# BQ24259RGER.net
KiCad netlist of a schematic drawn in Altium Designer
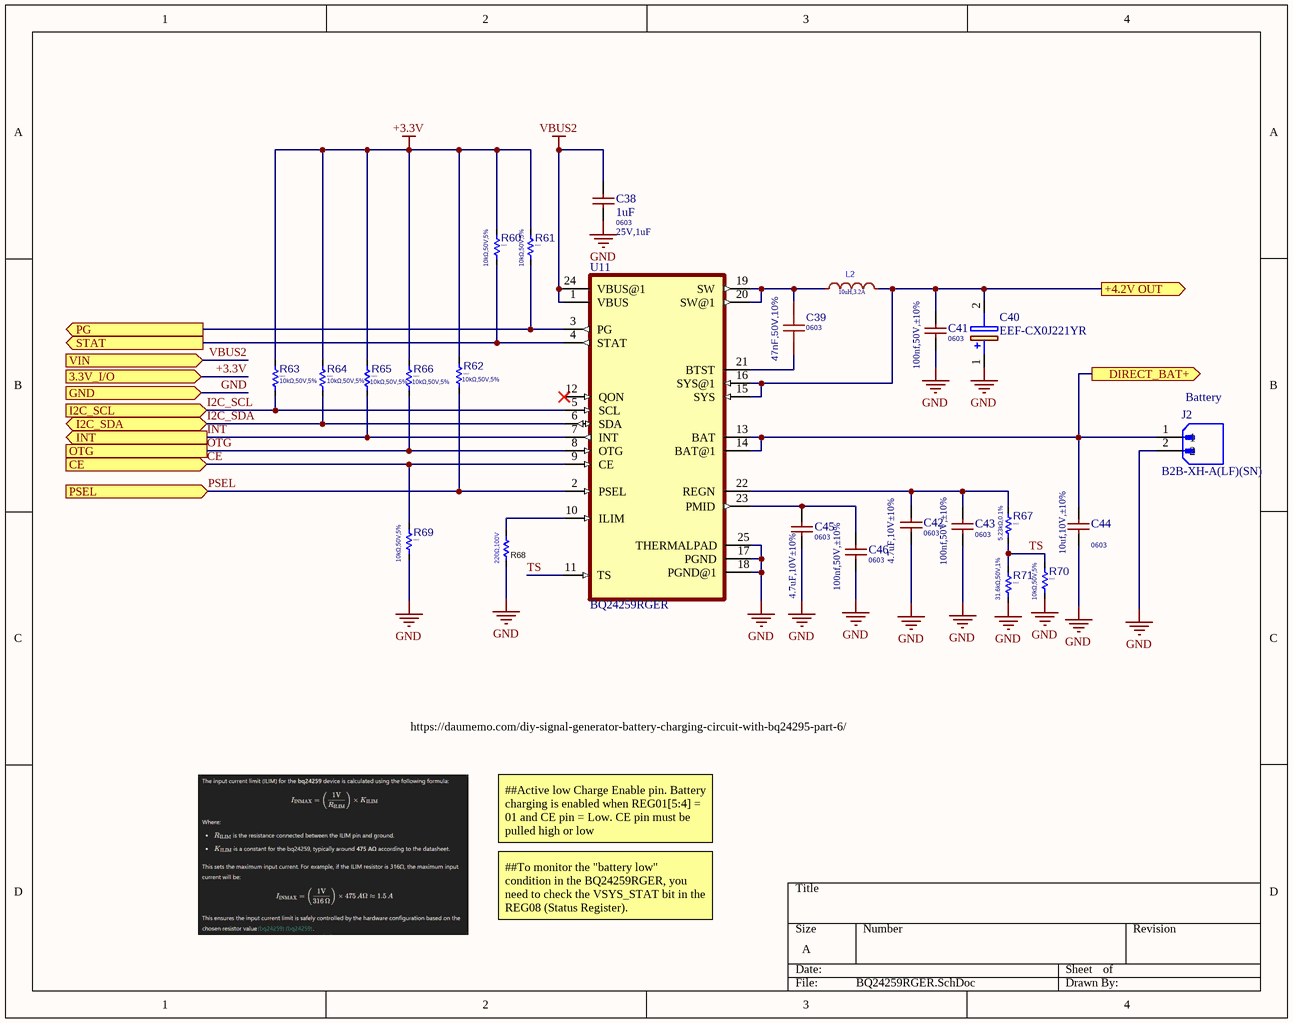
[diagram p0: BQ24259RGER.SchDoc]

(export (version "E")
  (design (tool "Eeschema 10.0.6"))
  (components
    (comp (ref "C38")
      (value "1uF")
      (footprint "CAPC1608X90N")
      (description "25V 1uF X7R ±10% 0603 Multilayer Ceramic Capacitors MLCC - SMD/SMT ROHS")
      (fields
        (field (name "MANUFACTURER") "FH (Guangdong Fenghua Advanced Tech)")
        (field (name "MPN") "0603B105K250NT")
        (field (name "PACKAGE") "0603")
        (field (name "ALTIUM_VALUE") "25V,1uF")
      )
      (libsource (lib "RCL") (part "0603B105K250NT"))
    )
    (comp (ref "C39")
      (value "47nF,50V,10%")
      (footprint "C0603")
      (description "50V 47nF X7R ±10% 0603 Multilayer Ceramic Capacitors MLCC - SMD/SMT ROHS")
      (fields
        (field (name "MANUFACTURER") "SAMSUNG")
        (field (name "MPN") "CL10B473KB8NNNC")
        (field (name "PACKAGE") "0603")
      )
      (libsource (lib "RCL") (part "CL10B473KB8NNNC"))
    )
    (comp (ref "C40")
      (value "EEF-CX0J221YR")
      (footprint "CAPPM7343X200N")
      (description "Capacitor Polarised")
      (libsource (lib "RCL") (part "EEF-CX0J221YR"))
    )
    (comp (ref "C41")
      (value "100nf,50V,±10%")
      (footprint "C0603")
      (description "50V 100nF X7R ±10% 0603 Multilayer Ceramic Capacitors MLCC - SMD/SMT ROHS")
      (fields
        (field (name "MPN") "603-CC603KRX7R9BB104")
        (field (name "MANUFACTURER") "KEMET")
        (field (name "PACKAGE") "0603")
      )
      (libsource (lib "RCL") (part "CC0603KRX7R9BB104"))
    )
    (comp (ref "C42")
      (value "4.7uF,10V±10%")
      (footprint "C0603")
      (description "10V 4.7uF X7R ±10% 0603 Multilayer Ceramic Capacitors MLCC - SMD/SMT ROHS")
      (fields
        (field (name "MPN") "CL10A475KQ8NNNC")
        (field (name "MANUFACTURER") "Samsung Electro-Mechanics")
        (field (name "PACKAGE") "0603")
      )
      (libsource (lib "RCL") (part "0603B475K100NT"))
    )
    (comp (ref "C43")
      (value "100nf,50V,±10%")
      (footprint "C0603")
      (description "50V 100nF X7R ±10% 0603 Multilayer Ceramic Capacitors MLCC - SMD/SMT ROHS")
      (fields
        (field (name "MPN") "603-CC603KRX7R9BB104")
        (field (name "MANUFACTURER") "KEMET")
        (field (name "PACKAGE") "0603")
      )
      (libsource (lib "RCL") (part "CC0603KRX7R9BB104"))
    )
    (comp (ref "C44")
      (value "10uf,10V,±10%")
      (footprint "C0603")
      (description "10V 10uF X7R ±10% 0603 Multilayer Ceramic Capacitors MLCC - SMD/SMT ROHS")
      (fields
        (field (name "MPN") "603-CC603KRX7R9BB104")
        (field (name "MANUFACTURER") "KEMET")
        (field (name "PACKAGE") "0603")
      )
      (libsource (lib "RCL") (part "GRM188Z71A106KA73D"))
    )
    (comp (ref "C45")
      (value "4.7uF,10V±10%")
      (footprint "C0603")
      (description "10V 4.7uF X7R ±10% 0603 Multilayer Ceramic Capacitors MLCC - SMD/SMT ROHS")
      (fields
        (field (name "MPN") "CL10A475KQ8NNNC")
        (field (name "MANUFACTURER") "Samsung Electro-Mechanics")
        (field (name "PACKAGE") "0603")
      )
      (libsource (lib "RCL") (part "0603B475K100NT"))
    )
    (comp (ref "C46")
      (value "100nf,50V,±10%")
      (footprint "C0603")
      (description "50V 100nF X7R ±10% 0603 Multilayer Ceramic Capacitors MLCC - SMD/SMT ROHS")
      (fields
        (field (name "MPN") "603-CC603KRX7R9BB104")
        (field (name "MANUFACTURER") "KEMET")
        (field (name "PACKAGE") "0603")
      )
      (libsource (lib "RCL") (part "CC0603KRX7R9BB104"))
    )
    (comp (ref "J2")
      (value "B2B-XH-A(LF)(SN)")
      (footprint "JST_B2B-XH-A(LF)(SN)")
      (description "Connector Header Through Hole 2 position 0.098 (2.50mm)")
      (fields (field (name "MANUFACTURER") "JST Sales America Inc."))
      (libsource (lib "connector_button") (part "B2B-XH-A(LF)(SN)"))
    )
    (comp (ref "L2")
      (value "10uH,3.2A")
      (footprint "inductor_SMD,5.2x5.4mm")
      (description "3.2A 10uH Integrated molded inductor ±20% 3.5A SMD,5.2x5.4mm Power Inductors ROHS")
      (fields (field (name "MANUFACTURER") "cjiang") (field (name "MPN") "FXL0530-100-M"))
      (libsource (lib "RCL") (part "FXL0530-100-M"))
    )
    (comp (ref "R60")
      (value "10kΩ,50V,5%")
      (footprint "R0402")
      (description "62.5mW Thick Film Resistors 50V ±100ppm/℃ ±5% 10kΩ 0402 Chip Resistor - Surface Mount ROHS")
      (fields
        (field (name "MANUFACTURER") "YAGEO")
        (field (name "MPN") "RC0402JR-0710KL")
        (field (name "PACKAGE") "0402")
      )
      (libsource (lib "RCL") (part "RC0402JR-0710KL"))
    )
    (comp (ref "R61")
      (value "10kΩ,50V,5%")
      (footprint "R0402")
      (description "62.5mW Thick Film Resistors 50V ±100ppm/℃ ±5% 10kΩ 0402 Chip Resistor - Surface Mount ROHS")
      (fields
        (field (name "MANUFACTURER") "YAGEO")
        (field (name "MPN") "RC0402JR-0710KL")
        (field (name "PACKAGE") "0402")
      )
      (libsource (lib "RCL") (part "RC0402JR-0710KL"))
    )
    (comp (ref "R62")
      (value "10kΩ,50V,5%")
      (footprint "R0402")
      (description "62.5mW Thick Film Resistors 50V ±100ppm/℃ ±5% 10kΩ 0402 Chip Resistor - Surface Mount ROHS")
      (fields
        (field (name "MANUFACTURER") "YAGEO")
        (field (name "MPN") "RC0402JR-0710KL")
        (field (name "PACKAGE") "0402")
      )
      (libsource (lib "RCL") (part "RC0402JR-0710KL"))
    )
    (comp (ref "R63")
      (value "10kΩ,50V,5%")
      (footprint "R0402")
      (description "62.5mW Thick Film Resistors 50V ±100ppm/℃ ±5% 10kΩ 0402 Chip Resistor - Surface Mount ROHS")
      (fields
        (field (name "MANUFACTURER") "YAGEO")
        (field (name "MPN") "RC0402JR-0710KL")
        (field (name "PACKAGE") "0402")
      )
      (libsource (lib "RCL") (part "RC0402JR-0710KL"))
    )
    (comp (ref "R64")
      (value "10kΩ,50V,5%")
      (footprint "R0402")
      (description "62.5mW Thick Film Resistors 50V ±100ppm/℃ ±5% 10kΩ 0402 Chip Resistor - Surface Mount ROHS")
      (fields
        (field (name "MANUFACTURER") "YAGEO")
        (field (name "MPN") "RC0402JR-0710KL")
        (field (name "PACKAGE") "0402")
      )
      (libsource (lib "RCL") (part "RC0402JR-0710KL"))
    )
    (comp (ref "R65")
      (value "10kΩ,50V,5%")
      (footprint "R0402")
      (description "62.5mW Thick Film Resistors 50V ±100ppm/℃ ±5% 10kΩ 0402 Chip Resistor - Surface Mount ROHS")
      (fields
        (field (name "MANUFACTURER") "YAGEO")
        (field (name "MPN") "RC0402JR-0710KL")
        (field (name "PACKAGE") "0402")
      )
      (libsource (lib "RCL") (part "RC0402JR-0710KL"))
    )
    (comp (ref "R66")
      (value "10kΩ,50V,5%")
      (footprint "R0402")
      (description "62.5mW Thick Film Resistors 50V ±100ppm/℃ ±5% 10kΩ 0402 Chip Resistor - Surface Mount ROHS")
      (fields
        (field (name "MANUFACTURER") "YAGEO")
        (field (name "MPN") "RC0402JR-0710KL")
        (field (name "PACKAGE") "0402")
      )
      (libsource (lib "RCL") (part "RC0402JR-0710KL"))
    )
    (comp (ref "R67")
      (value "5.23kΩ,0.1%")
      (footprint "R0402")
      (description "63mW Thin Film Resistor ±25ppm/℃ ±0.1% 5.23kΩ 0402 Chip Resistor - Surface Mount ROHS")
      (fields
        (field (name "MANUFACTURER") "YAGEO")
        (field (name "MPN") "RT0402BRD075K23L")
        (field (name "PACKAGE") "0402")
      )
      (libsource (lib "RCL") (part "RT0402BRD075K23L"))
    )
    (comp (ref "R68")
      (value "220Ω,100V")
      (footprint "R0402")
      (description "100mW Thick Film Resistors 100V ±100ppm/℃ ±1% 220Ω 0402 Chip Resistor - Surface Mount ROHS")
      (fields (field (name "MANUFACTURER") "PANASONIC") (field (name "MPN") "ERJ2RKF2200X"))
      (libsource (lib "RCL") (part "ERJ2RKF2200X"))
    )
    (comp (ref "R69")
      (value "10kΩ,50V,5%")
      (footprint "R0402")
      (description "62.5mW Thick Film Resistors 50V ±100ppm/℃ ±5% 10kΩ 0402 Chip Resistor - Surface Mount ROHS")
      (fields
        (field (name "MANUFACTURER") "YAGEO")
        (field (name "MPN") "RC0402JR-0710KL")
        (field (name "PACKAGE") "0402")
      )
      (libsource (lib "RCL") (part "RC0402JR-0710KL"))
    )
    (comp (ref "R70")
      (value "10kΩ,50V,5%")
      (footprint "R0402")
      (description "62.5mW Thick Film Resistors 50V ±100ppm/℃ ±5% 10kΩ 0402 Chip Resistor - Surface Mount ROHS")
      (fields
        (field (name "MANUFACTURER") "YAGEO")
        (field (name "MPN") "RC0402JR-0710KL")
        (field (name "PACKAGE") "0402")
      )
      (libsource (lib "RCL") (part "RC0402JR-0710KL"))
    )
    (comp (ref "R71")
      (value "31.6kΩ,50V,1%")
      (footprint "R0402")
      (description "62.5mW Thick Film Resistors 50V ±100ppm/℃ ±1% 31.6kΩ 0402 Chip Resistor - Surface Mount ROHS")
      (fields
        (field (name "MANUFACTURER") "YAGEO")
        (field (name "MPN") "RC0402FR-0731K6L")
        (field (name "PACKAGE") "0402")
      )
      (libsource (lib "RCL") (part "RC0402FR-0731K6L"))
    )
    (comp (ref "U11")
      (value "BQ24259RGER")
      (footprint "QFN50P400X400X100-25N")
      (description "I2C controlled 2A single cell USB NVDC-1 charger with adjustable voltageUSB OTG")
      (fields (field (name "DIGI-KEY_PART_NUMBER") "296-43322-2-ND") (field (name "MF") "Texas Instruments"))
      (libsource (lib "IC") (part "BQ24259RGER"))
    )
  )
  (nets
    (net (code "1") (name "+3.3V") (class "Default")
      (node (ref "R60") (pin "2") (pinfunction "2_2") (pintype "passive"))
      (node (ref "R61") (pin "2") (pinfunction "2_2") (pintype "passive"))
      (node (ref "R62") (pin "2") (pinfunction "2_2") (pintype "passive"))
      (node (ref "R63") (pin "2") (pinfunction "2_2") (pintype "passive"))
      (node (ref "R64") (pin "2") (pinfunction "2_2") (pintype "passive"))
      (node (ref "R65") (pin "2") (pinfunction "2_2") (pintype "passive"))
      (node (ref "R66") (pin "2") (pinfunction "2_2") (pintype "passive"))
    )
    (net (code "2") (name "/+4.2V OUT") (class "Default")
      (node (ref "C40") (pin "2") (pinfunction "-_2") (pintype "passive"))
      (node (ref "C41") (pin "2") (pinfunction "2_2") (pintype "passive"))
      (node (ref "L2") (pin "2") (pinfunction "2_2") (pintype "passive"))
      (node (ref "U11") (pin "15") (pinfunction "SYS_15") (pintype "input"))
      (node (ref "U11") (pin "16") (pinfunction "SYS@1_16") (pintype "input"))
    )
    (net (code "3") (name "/CE") (class "Default")
      (node (ref "R69") (pin "2") (pinfunction "2_2") (pintype "passive"))
      (node (ref "U11") (pin "9") (pinfunction "CE_9") (pintype "input"))
    )
    (net (code "4") (name "/DIRECT_BAT+") (class "Default")
      (node (ref "C44") (pin "2") (pinfunction "2_2") (pintype "passive"))
      (node (ref "J2") (pin "1") (pinfunction "1_1") (pintype "passive"))
      (node (ref "U11") (pin "13") (pinfunction "BAT_13") (pintype "power_in"))
      (node (ref "U11") (pin "14") (pinfunction "BAT@1_14") (pintype "power_in"))
    )
    (net (code "5") (name "/I2C_SCL") (class "Default")
      (node (ref "R63") (pin "1") (pinfunction "1_1") (pintype "passive"))
      (node (ref "U11") (pin "5") (pinfunction "SCL_5") (pintype "input"))
    )
    (net (code "6") (name "/I2C_SDA") (class "Default")
      (node (ref "R64") (pin "1") (pinfunction "1_1") (pintype "passive"))
      (node (ref "U11") (pin "6") (pinfunction "SDA_6") (pintype "bidirectional"))
    )
    (net (code "7") (name "/INT") (class "Default")
      (node (ref "R65") (pin "1") (pinfunction "1_1") (pintype "passive"))
      (node (ref "U11") (pin "7") (pinfunction "INT_7") (pintype "output"))
    )
    (net (code "8") (name "/OTG") (class "Default")
      (node (ref "R66") (pin "1") (pinfunction "1_1") (pintype "passive"))
      (node (ref "U11") (pin "8") (pinfunction "OTG_8") (pintype "input"))
    )
    (net (code "9") (name "/PG") (class "Default")
      (node (ref "R61") (pin "1") (pinfunction "1_1") (pintype "passive"))
      (node (ref "U11") (pin "3") (pinfunction "PG_3") (pintype "output"))
    )
    (net (code "10") (name "/PSEL") (class "Default")
      (node (ref "R62") (pin "1") (pinfunction "1_1") (pintype "passive"))
      (node (ref "U11") (pin "2") (pinfunction "PSEL_2") (pintype "input"))
    )
    (net (code "11") (name "/STAT") (class "Default")
      (node (ref "R60") (pin "1") (pinfunction "1_1") (pintype "passive"))
      (node (ref "U11") (pin "4") (pinfunction "STAT_4") (pintype "output"))
    )
    (net (code "12") (name "/TS") (class "Default")
      (node (ref "R67") (pin "1") (pinfunction "1_1") (pintype "passive"))
      (node (ref "R70") (pin "2") (pinfunction "2_2") (pintype "passive"))
      (node (ref "R71") (pin "2") (pinfunction "2_2") (pintype "passive"))
      (node (ref "U11") (pin "11") (pinfunction "TS_11") (pintype "input"))
    )
    (net (code "13") (name "GND") (class "Default")
      (node (ref "C38") (pin "1") (pinfunction "1_1") (pintype "passive"))
      (node (ref "C40") (pin "1") (pinfunction "+_1") (pintype "passive"))
      (node (ref "C41") (pin "1") (pinfunction "1_1") (pintype "passive"))
      (node (ref "C42") (pin "1") (pinfunction "1_1") (pintype "passive"))
      (node (ref "C43") (pin "1") (pinfunction "1_1") (pintype "passive"))
      (node (ref "C44") (pin "1") (pinfunction "1_1") (pintype "passive"))
      (node (ref "C45") (pin "1") (pinfunction "1_1") (pintype "passive"))
      (node (ref "C46") (pin "1") (pinfunction "1_1") (pintype "passive"))
      (node (ref "J2") (pin "2") (pinfunction "2_2") (pintype "passive"))
      (node (ref "R68") (pin "1") (pinfunction "1_1") (pintype "passive"))
      (node (ref "R69") (pin "1") (pinfunction "1_1") (pintype "passive"))
      (node (ref "R70") (pin "1") (pinfunction "1_1") (pintype "passive"))
      (node (ref "R71") (pin "1") (pinfunction "1_1") (pintype "passive"))
      (node (ref "U11") (pin "17") (pinfunction "PGND_17") (pintype "power_in"))
      (node (ref "U11") (pin "18") (pinfunction "PGND@1_18") (pintype "power_in"))
      (node (ref "U11") (pin "25") (pinfunction "THERMALPAD_25") (pintype "power_in"))
    )
    (net (code "14") (name "Net-(U11-BTST)") (class "Default")
      (node (ref "C39") (pin "1") (pinfunction "1_1") (pintype "passive"))
      (node (ref "U11") (pin "21") (pinfunction "BTST_21") (pintype "power_in"))
    )
    (net (code "15") (name "Net-(U11-ILIM)") (class "Default")
      (node (ref "R68") (pin "2") (pinfunction "2_2") (pintype "passive"))
      (node (ref "U11") (pin "10") (pinfunction "ILIM_10") (pintype "input"))
    )
    (net (code "16") (name "Net-(U11-PMID)") (class "Default")
      (node (ref "C45") (pin "2") (pinfunction "2_2") (pintype "passive"))
      (node (ref "C46") (pin "2") (pinfunction "2_2") (pintype "passive"))
      (node (ref "U11") (pin "23") (pinfunction "PMID_23") (pintype "output"))
    )
    (net (code "17") (name "Net-(U11-REGN)") (class "Default")
      (node (ref "C42") (pin "2") (pinfunction "2_2") (pintype "passive"))
      (node (ref "C43") (pin "2") (pinfunction "2_2") (pintype "passive"))
      (node (ref "R67") (pin "2") (pinfunction "2_2") (pintype "passive"))
      (node (ref "U11") (pin "22") (pinfunction "REGN_22") (pintype "power_in"))
    )
    (net (code "18") (name "Net-(U11-SW)") (class "Default")
      (node (ref "C39") (pin "2") (pinfunction "2_2") (pintype "passive"))
      (node (ref "L2") (pin "1") (pinfunction "1_1") (pintype "passive"))
      (node (ref "U11") (pin "19") (pinfunction "SW_19") (pintype "output"))
      (node (ref "U11") (pin "20") (pinfunction "SW@1_20") (pintype "output"))
    )
    (net (code "19") (name "VBUS2") (class "Default")
      (node (ref "C38") (pin "2") (pinfunction "2_2") (pintype "passive"))
      (node (ref "U11") (pin "1") (pinfunction "VBUS_1") (pintype "power_in"))
      (node (ref "U11") (pin "24") (pinfunction "VBUS@1_24") (pintype "power_in"))
    )
    (net (code "20") (name "unconnected-(U11-QON-Pad12)") (class "Default")
      (node (ref "U11") (pin "12") (pinfunction "QON_12") (pintype "input+no_connect"))
    )
  )
)
